# cellSwitcher_li_ion_V6.net
KiCad netlist of a schematic drawn in EAGLE
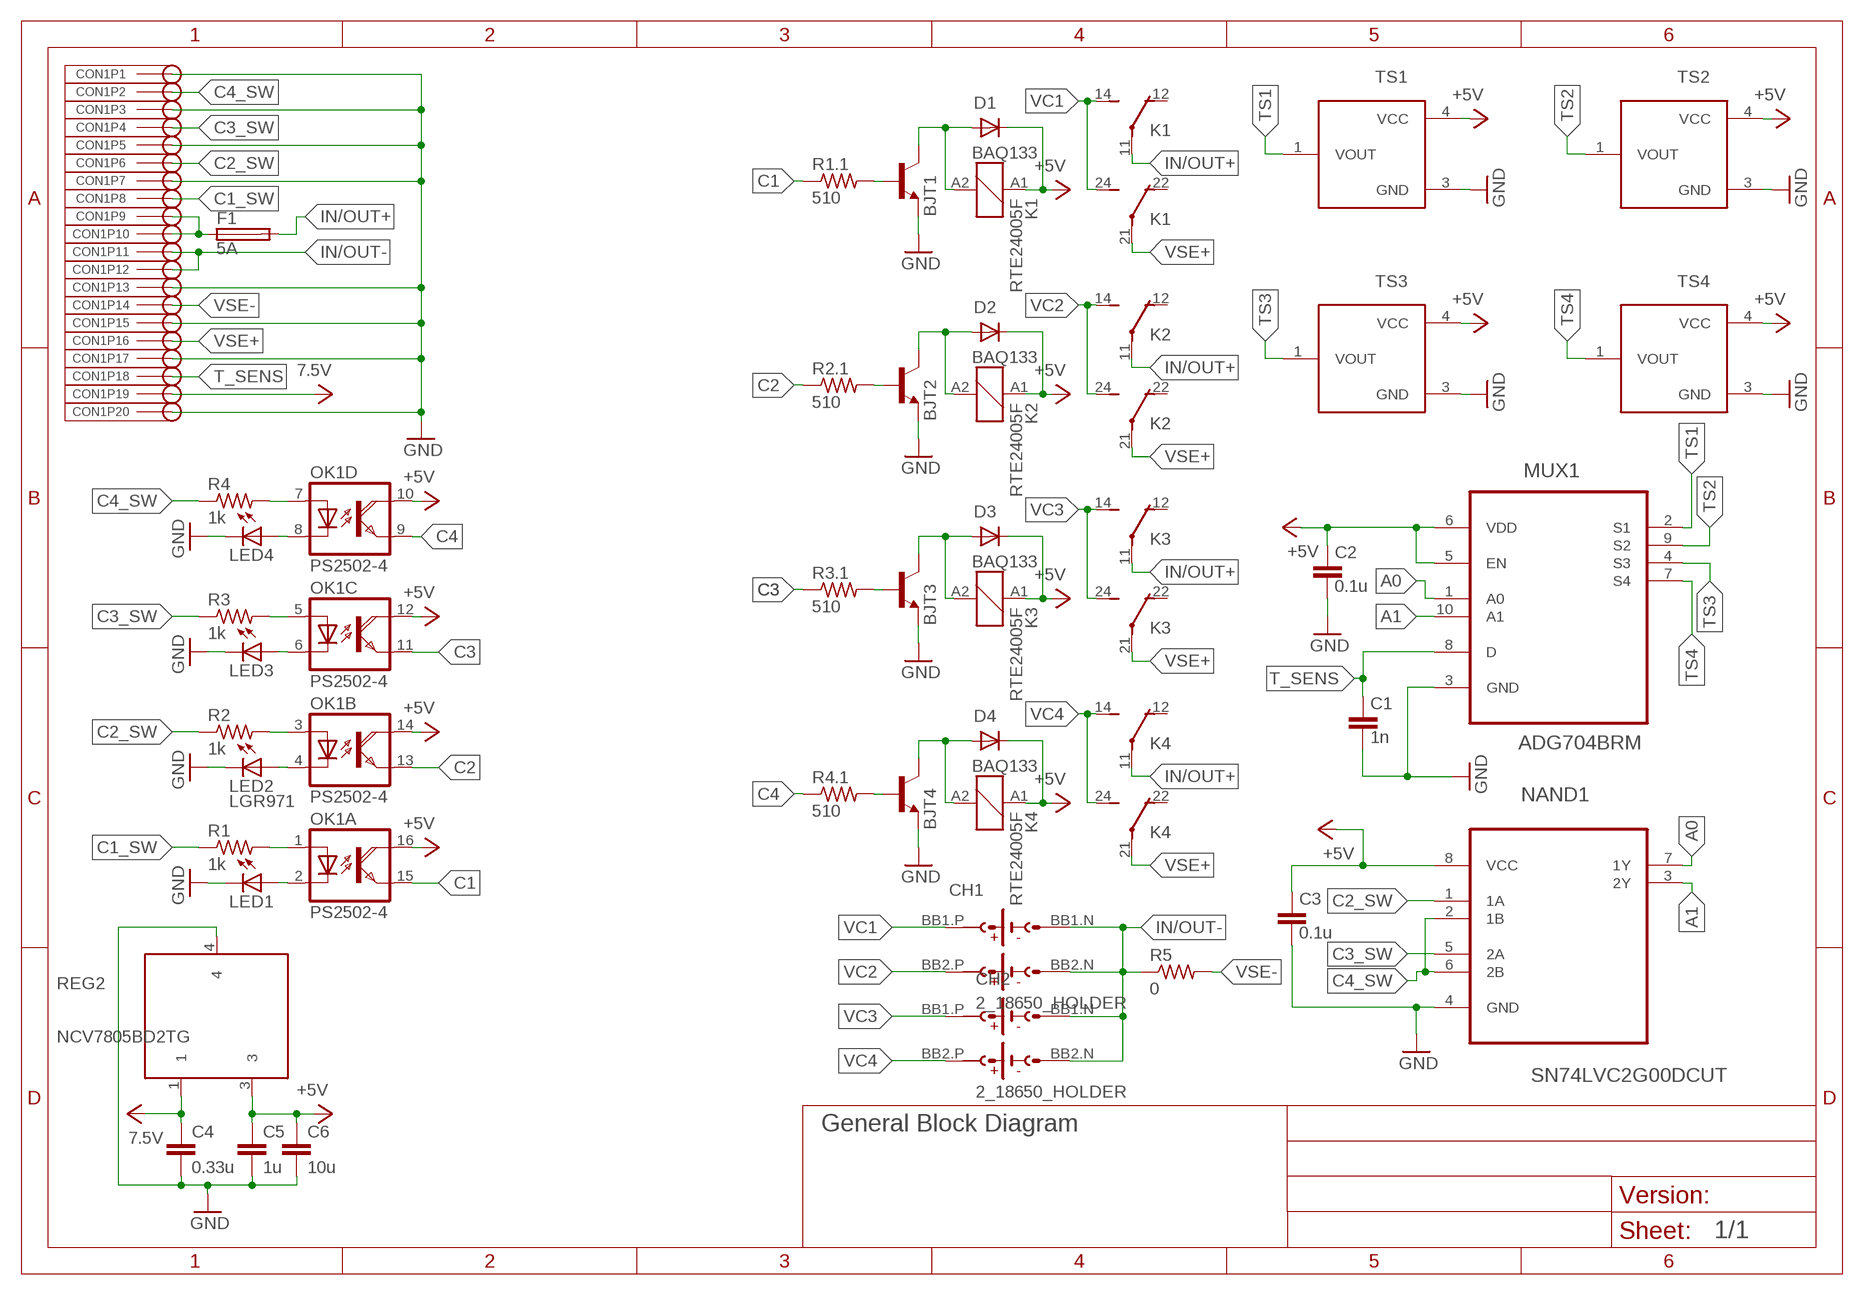
[diagram p0: schematic, sheet 1]

(export (version "E")
  (design (tool "Eeschema 10.0.6"))
  (components
    (comp (ref "BJT1")
      (value "BC818K-40")
      (footprint "eagle-import:SOT-23")
      (libsource (lib "eagle-import") (part "BC818K-40"))
    )
    (comp (ref "BJT2")
      (value "BC818K-40")
      (footprint "eagle-import:SOT-23")
      (libsource (lib "eagle-import") (part "BC818K-40"))
    )
    (comp (ref "BJT3")
      (value "BC818K-40")
      (footprint "eagle-import:SOT-23")
      (libsource (lib "eagle-import") (part "BC818K-40"))
    )
    (comp (ref "BJT4")
      (value "BC818K-40")
      (footprint "eagle-import:SOT-23")
      (libsource (lib "eagle-import") (part "BC818K-40"))
    )
    (comp (ref "C1")
      (value "1n")
      (footprint "eagle-import:C0603")
      (libsource (lib "eagle-import") (part "NONPOL_CAP-0603"))
    )
    (comp (ref "C2")
      (value "0.1u")
      (footprint "eagle-import:C0603")
      (libsource (lib "eagle-import") (part "NONPOL_CAP-0603"))
    )
    (comp (ref "C3")
      (value "0.1u")
      (footprint "eagle-import:C0603")
      (libsource (lib "eagle-import") (part "NONPOL_CAP-0603"))
    )
    (comp (ref "C4")
      (value "0.33u")
      (footprint "eagle-import:C0603")
      (libsource (lib "eagle-import") (part "NONPOL_CAP-0603"))
    )
    (comp (ref "C5")
      (value "1u")
      (footprint "eagle-import:C0603")
      (libsource (lib "eagle-import") (part "NONPOL_CAP-0603"))
    )
    (comp (ref "C6")
      (value "10u")
      (footprint "eagle-import:C0603")
      (libsource (lib "eagle-import") (part "NONPOL_CAP-0603"))
    )
    (comp (ref "CH1")
      (value "2_18650_HOLDER")
      (footprint "eagle-import:2_18650_HOLDER")
      (libsource (lib "eagle-import") (part "2_18650_HOLDER"))
    )
    (comp (ref "CH2")
      (value "2_18650_HOLDER")
      (footprint "eagle-import:2_18650_HOLDER")
      (libsource (lib "eagle-import") (part "2_18650_HOLDER"))
    )
    (comp (ref "CON1")
      (value "TMM-110-01-F-D-RA")
      (footprint "eagle-import:TMM-110-01-F-D-RA")
      (libsource (lib "eagle-import") (part "TMM-110-01-F-D-RA"))
    )
    (comp (ref "D1")
      (value "BAQ133")
      (footprint "eagle-import:SOD08")
      (libsource (lib "eagle-import") (part "DIODE-BAQ133-GS08"))
    )
    (comp (ref "D2")
      (value "BAQ133")
      (footprint "eagle-import:SOD08")
      (libsource (lib "eagle-import") (part "DIODE-BAQ133-GS08"))
    )
    (comp (ref "D3")
      (value "BAQ133")
      (footprint "eagle-import:SOD08")
      (libsource (lib "eagle-import") (part "DIODE-BAQ133-GS08"))
    )
    (comp (ref "D4")
      (value "BAQ133")
      (footprint "eagle-import:SOD08")
      (libsource (lib "eagle-import") (part "DIODE-BAQ133-GS08"))
    )
    (comp (ref "F1")
      (value "5A")
      (footprint "eagle-import:SH22,5")
      (fields (field (name "MF") "SCHURTER") (field (name "MPN") "0031.8201"))
      (libsource (lib "eagle-import") (part "FUSEHOLDER"))
    )
    (comp (ref "K1")
      (value "RTE24005F")
      (footprint "eagle-import:RTE24005F")
      (libsource (lib "eagle-import") (part "RTE24005F"))
    )
    (comp (ref "K2")
      (value "RTE24005F")
      (footprint "eagle-import:RTE24005F")
      (libsource (lib "eagle-import") (part "RTE24005F"))
    )
    (comp (ref "K3")
      (value "RTE24005F")
      (footprint "eagle-import:RTE24005F")
      (libsource (lib "eagle-import") (part "RTE24005F"))
    )
    (comp (ref "K4")
      (value "RTE24005F")
      (footprint "eagle-import:RTE24005F")
      (libsource (lib "eagle-import") (part "RTE24005F"))
    )
    (comp (ref "LED1")
      (value "LGR971")
      (footprint "eagle-import:SML0805")
      (libsource (lib "eagle-import") (part "LGR971"))
    )
    (comp (ref "LED2")
      (value "LGR971")
      (footprint "eagle-import:SML0805")
      (libsource (lib "eagle-import") (part "LGR971"))
    )
    (comp (ref "LED3")
      (value "LGR971")
      (footprint "eagle-import:SML0805")
      (libsource (lib "eagle-import") (part "LGR971"))
    )
    (comp (ref "LED4")
      (value "LGR971")
      (footprint "eagle-import:SML0805")
      (libsource (lib "eagle-import") (part "LGR971"))
    )
    (comp (ref "MUX1")
      (value "ADG704BRM")
      (footprint "eagle-import:MSOP10")
      (fields (field (name "MPN") "ADG704BRM-REEL"))
      (libsource (lib "eagle-import") (part "ADG704BRM"))
    )
    (comp (ref "NAND1")
      (value "SN74LVC2G00DCUT")
      (footprint "eagle-import:VSSOP-8")
      (libsource (lib "eagle-import") (part "SN74LVC2G00DCUT"))
    )
    (comp (ref "OK1")
      (value "PS2502-4")
      (footprint "eagle-import:DIL16")
      (libsource (lib "eagle-import") (part "PS2502-4"))
    )
    (comp (ref "R1")
      (value "1k")
      (footprint "eagle-import:R0603")
      (libsource (lib "eagle-import") (part "RESISTOR-0603"))
    )
    (comp (ref "R1.1")
      (value "510")
      (footprint "eagle-import:R0603")
      (libsource (lib "eagle-import") (part "RESISTOR-0603"))
    )
    (comp (ref "R2")
      (value "1k")
      (footprint "eagle-import:R0603")
      (libsource (lib "eagle-import") (part "RESISTOR-0603"))
    )
    (comp (ref "R2.1")
      (value "510")
      (footprint "eagle-import:R0603")
      (libsource (lib "eagle-import") (part "RESISTOR-0603"))
    )
    (comp (ref "R3")
      (value "1k")
      (footprint "eagle-import:R0603")
      (libsource (lib "eagle-import") (part "RESISTOR-0603"))
    )
    (comp (ref "R3.1")
      (value "510")
      (footprint "eagle-import:R0603")
      (libsource (lib "eagle-import") (part "RESISTOR-0603"))
    )
    (comp (ref "R4")
      (value "1k")
      (footprint "eagle-import:R0603")
      (libsource (lib "eagle-import") (part "RESISTOR-0603"))
    )
    (comp (ref "R4.1")
      (value "510")
      (footprint "eagle-import:R0603")
      (libsource (lib "eagle-import") (part "RESISTOR-0603"))
    )
    (comp (ref "R5")
      (value "0")
      (footprint "eagle-import:R0603")
      (libsource (lib "eagle-import") (part "RESISTOR-0603"))
    )
    (comp (ref "REG2")
      (value "NCV7805BD2TG")
      (footprint "eagle-import:D2PAK-3")
      (libsource (lib "eagle-import") (part "NCV7805BD2TG"))
    )
    (comp (ref "TS1")
      (value "STLM20DD9F")
      (footprint "eagle-import:UDFN-4L")
      (libsource (lib "eagle-import") (part "STLM20DD9F"))
    )
    (comp (ref "TS2")
      (value "STLM20DD9F")
      (footprint "eagle-import:UDFN-4L")
      (libsource (lib "eagle-import") (part "STLM20DD9F"))
    )
    (comp (ref "TS3")
      (value "STLM20DD9F")
      (footprint "eagle-import:UDFN-4L")
      (libsource (lib "eagle-import") (part "STLM20DD9F"))
    )
    (comp (ref "TS4")
      (value "STLM20DD9F")
      (footprint "eagle-import:UDFN-4L")
      (libsource (lib "eagle-import") (part "STLM20DD9F"))
    )
  )
  (nets
    (net (code "1") (name "+5V") (class "Default")
      (node (ref "C2") (pin "1") (pinfunction "1_1") (pintype "passive"))
      (node (ref "C3") (pin "1") (pinfunction "1_1") (pintype "passive"))
      (node (ref "C5") (pin "1") (pinfunction "1_1") (pintype "passive"))
      (node (ref "C6") (pin "1") (pinfunction "1_1") (pintype "passive"))
      (node (ref "D1") (pin "C") (pinfunction "C_C") (pintype "passive"))
      (node (ref "D2") (pin "C") (pinfunction "C_C") (pintype "passive"))
      (node (ref "D3") (pin "C") (pinfunction "C_C") (pintype "passive"))
      (node (ref "D4") (pin "C") (pinfunction "C_C") (pintype "passive"))
      (node (ref "K1") (pin "A1") (pinfunction "1_A1") (pintype "passive"))
      (node (ref "K2") (pin "A1") (pinfunction "1_A1") (pintype "passive"))
      (node (ref "K3") (pin "A1") (pinfunction "1_A1") (pintype "passive"))
      (node (ref "K4") (pin "A1") (pinfunction "1_A1") (pintype "passive"))
      (node (ref "MUX1") (pin "5") (pinfunction "EN_5") (pintype "input"))
      (node (ref "MUX1") (pin "6") (pinfunction "VDD_6") (pintype "power_in"))
      (node (ref "NAND1") (pin "8") (pinfunction "VCC_8") (pintype "power_in"))
      (node (ref "OK1") (pin "10") (pinfunction "COL_10") (pintype "passive"))
      (node (ref "OK1") (pin "12") (pinfunction "COL_12") (pintype "passive"))
      (node (ref "OK1") (pin "14") (pinfunction "COL_14") (pintype "passive"))
      (node (ref "OK1") (pin "16") (pinfunction "COL_16") (pintype "passive"))
      (node (ref "REG2") (pin "3") (pinfunction "3_3") (pintype "bidirectional"))
      (node (ref "TS1") (pin "4") (pinfunction "VCC_4") (pintype "bidirectional"))
      (node (ref "TS2") (pin "4") (pinfunction "VCC_4") (pintype "bidirectional"))
      (node (ref "TS3") (pin "4") (pinfunction "VCC_4") (pintype "bidirectional"))
      (node (ref "TS4") (pin "4") (pinfunction "VCC_4") (pintype "bidirectional"))
    )
    (net (code "2") (name "7.5V") (class "Default")
      (node (ref "C4") (pin "1") (pinfunction "1_1") (pintype "passive"))
      (node (ref "CON1") (pin "19") (pinfunction "PIN_19") (pintype "bidirectional"))
      (node (ref "REG2") (pin "1") (pinfunction "1_1") (pintype "bidirectional"))
    )
    (net (code "3") (name "A0") (class "Default")
      (node (ref "MUX1") (pin "1") (pinfunction "A0_1") (pintype "input"))
      (node (ref "NAND1") (pin "7") (pinfunction "1Y_7") (pintype "output"))
    )
    (net (code "4") (name "A1") (class "Default")
      (node (ref "MUX1") (pin "10") (pinfunction "A1_10") (pintype "input"))
      (node (ref "NAND1") (pin "3") (pinfunction "2Y_3") (pintype "output"))
    )
    (net (code "5") (name "C1") (class "Default")
      (node (ref "OK1") (pin "15") (pinfunction "EMI_15") (pintype "passive"))
      (node (ref "R1.1") (pin "1") (pinfunction "1_1") (pintype "passive"))
    )
    (net (code "6") (name "C1_SW") (class "Default")
      (node (ref "CON1") (pin "8") (pinfunction "PIN_8") (pintype "bidirectional"))
      (node (ref "R1") (pin "1") (pinfunction "1_1") (pintype "passive"))
    )
    (net (code "7") (name "C2") (class "Default")
      (node (ref "OK1") (pin "13") (pinfunction "EMI_13") (pintype "passive"))
      (node (ref "R2.1") (pin "1") (pinfunction "1_1") (pintype "passive"))
    )
    (net (code "8") (name "C2_SW") (class "Default")
      (node (ref "CON1") (pin "6") (pinfunction "PIN_6") (pintype "bidirectional"))
      (node (ref "NAND1") (pin "1") (pinfunction "1A_1") (pintype "input"))
      (node (ref "R2") (pin "1") (pinfunction "1_1") (pintype "passive"))
    )
    (net (code "9") (name "C3") (class "Default")
      (node (ref "OK1") (pin "11") (pinfunction "EMI_11") (pintype "passive"))
      (node (ref "R3.1") (pin "1") (pinfunction "1_1") (pintype "passive"))
    )
    (net (code "10") (name "C3_SW") (class "Default")
      (node (ref "CON1") (pin "4") (pinfunction "PIN_4") (pintype "bidirectional"))
      (node (ref "NAND1") (pin "5") (pinfunction "2A_5") (pintype "input"))
      (node (ref "R3") (pin "1") (pinfunction "1_1") (pintype "passive"))
    )
    (net (code "11") (name "C4") (class "Default")
      (node (ref "OK1") (pin "9") (pinfunction "EMI_9") (pintype "passive"))
      (node (ref "R4.1") (pin "1") (pinfunction "1_1") (pintype "passive"))
    )
    (net (code "12") (name "C4_SW") (class "Default")
      (node (ref "CON1") (pin "2") (pinfunction "PIN_2") (pintype "bidirectional"))
      (node (ref "NAND1") (pin "2") (pinfunction "1B_2") (pintype "input"))
      (node (ref "NAND1") (pin "6") (pinfunction "2B_6") (pintype "input"))
      (node (ref "R4") (pin "1") (pinfunction "1_1") (pintype "passive"))
    )
    (net (code "13") (name "GND") (class "Default")
      (node (ref "BJT1") (pin "2") (pinfunction "E_2") (pintype "passive"))
      (node (ref "BJT2") (pin "2") (pinfunction "E_2") (pintype "passive"))
      (node (ref "BJT3") (pin "2") (pinfunction "E_2") (pintype "passive"))
      (node (ref "BJT4") (pin "2") (pinfunction "E_2") (pintype "passive"))
      (node (ref "C1") (pin "2") (pinfunction "2_2") (pintype "passive"))
      (node (ref "C2") (pin "2") (pinfunction "2_2") (pintype "passive"))
      (node (ref "C3") (pin "2") (pinfunction "2_2") (pintype "passive"))
      (node (ref "C4") (pin "2") (pinfunction "2_2") (pintype "passive"))
      (node (ref "C5") (pin "2") (pinfunction "2_2") (pintype "passive"))
      (node (ref "C6") (pin "2") (pinfunction "2_2") (pintype "passive"))
      (node (ref "CON1") (pin "1") (pinfunction "PIN_1") (pintype "bidirectional"))
      (node (ref "CON1") (pin "13") (pinfunction "PIN_13") (pintype "bidirectional"))
      (node (ref "CON1") (pin "15") (pinfunction "PIN_15") (pintype "bidirectional"))
      (node (ref "CON1") (pin "17") (pinfunction "PIN_17") (pintype "bidirectional"))
      (node (ref "CON1") (pin "20") (pinfunction "PIN_20") (pintype "bidirectional"))
      (node (ref "CON1") (pin "3") (pinfunction "PIN_3") (pintype "bidirectional"))
      (node (ref "CON1") (pin "5") (pinfunction "PIN_5") (pintype "bidirectional"))
      (node (ref "CON1") (pin "7") (pinfunction "PIN_7") (pintype "bidirectional"))
      (node (ref "LED1") (pin "C") (pinfunction "C_C") (pintype "passive"))
      (node (ref "LED2") (pin "C") (pinfunction "C_C") (pintype "passive"))
      (node (ref "LED3") (pin "C") (pinfunction "C_C") (pintype "passive"))
      (node (ref "LED4") (pin "C") (pinfunction "C_C") (pintype "passive"))
      (node (ref "MUX1") (pin "3") (pinfunction "GND_3") (pintype "passive"))
      (node (ref "NAND1") (pin "4") (pinfunction "GND_4") (pintype "passive"))
      (node (ref "REG2") (pin "4") (pinfunction "4_4") (pintype "bidirectional"))
      (node (ref "TS1") (pin "3") (pinfunction "GND_3") (pintype "bidirectional"))
      (node (ref "TS2") (pin "3") (pinfunction "GND_3") (pintype "bidirectional"))
      (node (ref "TS3") (pin "3") (pinfunction "GND_3") (pintype "bidirectional"))
      (node (ref "TS4") (pin "3") (pinfunction "GND_3") (pintype "bidirectional"))
    )
    (net (code "14") (name "IN{slash}OUT+") (class "Default")
      (node (ref "F1") (pin "2") (pinfunction "2_2") (pintype "passive"))
      (node (ref "K1") (pin "11") (pinfunction "COM_11") (pintype "passive"))
      (node (ref "K2") (pin "11") (pinfunction "COM_11") (pintype "passive"))
      (node (ref "K3") (pin "11") (pinfunction "COM_11") (pintype "passive"))
      (node (ref "K4") (pin "11") (pinfunction "COM_11") (pintype "passive"))
    )
    (net (code "15") (name "IN{slash}OUT-") (class "Default")
      (node (ref "CH1") (pin "BB1.N") (pinfunction "B1.N_BB1.N") (pintype "bidirectional"))
      (node (ref "CH1") (pin "BB2.N") (pinfunction "B2.N_BB2.N") (pintype "bidirectional"))
      (node (ref "CH2") (pin "BB1.N") (pinfunction "B1.N_BB1.N") (pintype "bidirectional"))
      (node (ref "CH2") (pin "BB2.N") (pinfunction "B2.N_BB2.N") (pintype "bidirectional"))
      (node (ref "CON1") (pin "11") (pinfunction "PIN_11") (pintype "bidirectional"))
      (node (ref "CON1") (pin "12") (pinfunction "PIN_12") (pintype "bidirectional"))
      (node (ref "R5") (pin "1") (pinfunction "1_1") (pintype "passive"))
    )
    (net (code "16") (name "Net-(BJT1-B)") (class "Default")
      (node (ref "BJT1") (pin "1") (pinfunction "B_1") (pintype "passive"))
      (node (ref "R1.1") (pin "2") (pinfunction "2_2") (pintype "passive"))
    )
    (net (code "17") (name "Net-(BJT1-C)") (class "Default")
      (node (ref "BJT1") (pin "3") (pinfunction "C_3") (pintype "passive"))
      (node (ref "D1") (pin "A") (pinfunction "A_A") (pintype "passive"))
      (node (ref "K1") (pin "A2") (pinfunction "2_A2") (pintype "passive"))
    )
    (net (code "18") (name "Net-(BJT2-B)") (class "Default")
      (node (ref "BJT2") (pin "1") (pinfunction "B_1") (pintype "passive"))
      (node (ref "R2.1") (pin "2") (pinfunction "2_2") (pintype "passive"))
    )
    (net (code "19") (name "Net-(BJT2-C)") (class "Default")
      (node (ref "BJT2") (pin "3") (pinfunction "C_3") (pintype "passive"))
      (node (ref "D2") (pin "A") (pinfunction "A_A") (pintype "passive"))
      (node (ref "K2") (pin "A2") (pinfunction "2_A2") (pintype "passive"))
    )
    (net (code "20") (name "Net-(BJT3-B)") (class "Default")
      (node (ref "BJT3") (pin "1") (pinfunction "B_1") (pintype "passive"))
      (node (ref "R3.1") (pin "2") (pinfunction "2_2") (pintype "passive"))
    )
    (net (code "21") (name "Net-(BJT3-C)") (class "Default")
      (node (ref "BJT3") (pin "3") (pinfunction "C_3") (pintype "passive"))
      (node (ref "D3") (pin "A") (pinfunction "A_A") (pintype "passive"))
      (node (ref "K3") (pin "A2") (pinfunction "2_A2") (pintype "passive"))
    )
    (net (code "22") (name "Net-(BJT4-B)") (class "Default")
      (node (ref "BJT4") (pin "1") (pinfunction "B_1") (pintype "passive"))
      (node (ref "R4.1") (pin "2") (pinfunction "2_2") (pintype "passive"))
    )
    (net (code "23") (name "Net-(BJT4-C)") (class "Default")
      (node (ref "BJT4") (pin "3") (pinfunction "C_3") (pintype "passive"))
      (node (ref "D4") (pin "A") (pinfunction "A_A") (pintype "passive"))
      (node (ref "K4") (pin "A2") (pinfunction "2_A2") (pintype "passive"))
    )
    (net (code "24") (name "Net-(CON1B-PIN)") (class "Default")
      (node (ref "CON1") (pin "10") (pinfunction "PIN_10") (pintype "bidirectional"))
      (node (ref "CON1") (pin "9") (pinfunction "PIN_9") (pintype "bidirectional"))
      (node (ref "F1") (pin "1") (pinfunction "1_1") (pintype "passive"))
    )
    (net (code "25") (name "Net-(OK1A-A)") (class "Default")
      (node (ref "OK1") (pin "1") (pinfunction "A_1") (pintype "passive"))
      (node (ref "R1") (pin "2") (pinfunction "2_2") (pintype "passive"))
    )
    (net (code "26") (name "Net-(OK1A-C)") (class "Default")
      (node (ref "LED1") (pin "A") (pinfunction "A_A") (pintype "passive"))
      (node (ref "OK1") (pin "2") (pinfunction "C_2") (pintype "passive"))
    )
    (net (code "27") (name "Net-(OK1B-A)") (class "Default")
      (node (ref "OK1") (pin "3") (pinfunction "A_3") (pintype "passive"))
      (node (ref "R2") (pin "2") (pinfunction "2_2") (pintype "passive"))
    )
    (net (code "28") (name "Net-(OK1B-C)") (class "Default")
      (node (ref "LED2") (pin "A") (pinfunction "A_A") (pintype "passive"))
      (node (ref "OK1") (pin "4") (pinfunction "C_4") (pintype "passive"))
    )
    (net (code "29") (name "Net-(OK1C-A)") (class "Default")
      (node (ref "OK1") (pin "5") (pinfunction "A_5") (pintype "passive"))
      (node (ref "R3") (pin "2") (pinfunction "2_2") (pintype "passive"))
    )
    (net (code "30") (name "Net-(OK1C-C)") (class "Default")
      (node (ref "LED3") (pin "A") (pinfunction "A_A") (pintype "passive"))
      (node (ref "OK1") (pin "6") (pinfunction "C_6") (pintype "passive"))
    )
    (net (code "31") (name "Net-(OK1D-A)") (class "Default")
      (node (ref "OK1") (pin "7") (pinfunction "A_7") (pintype "passive"))
      (node (ref "R4") (pin "2") (pinfunction "2_2") (pintype "passive"))
    )
    (net (code "32") (name "Net-(OK1D-C)") (class "Default")
      (node (ref "LED4") (pin "A") (pinfunction "A_A") (pintype "passive"))
      (node (ref "OK1") (pin "8") (pinfunction "C_8") (pintype "passive"))
    )
    (net (code "33") (name "TS1") (class "Default")
      (node (ref "MUX1") (pin "2") (pinfunction "S1_2") (pintype "bidirectional"))
      (node (ref "TS1") (pin "1") (pinfunction "VOUT_1") (pintype "bidirectional"))
    )
    (net (code "34") (name "TS2") (class "Default")
      (node (ref "MUX1") (pin "9") (pinfunction "S2_9") (pintype "bidirectional"))
      (node (ref "TS2") (pin "1") (pinfunction "VOUT_1") (pintype "bidirectional"))
    )
    (net (code "35") (name "TS3") (class "Default")
      (node (ref "MUX1") (pin "4") (pinfunction "S3_4") (pintype "bidirectional"))
      (node (ref "TS3") (pin "1") (pinfunction "VOUT_1") (pintype "bidirectional"))
    )
    (net (code "36") (name "TS4") (class "Default")
      (node (ref "MUX1") (pin "7") (pinfunction "S4_7") (pintype "bidirectional"))
      (node (ref "TS4") (pin "1") (pinfunction "VOUT_1") (pintype "bidirectional"))
    )
    (net (code "37") (name "T_SENS") (class "Default")
      (node (ref "C1") (pin "1") (pinfunction "1_1") (pintype "passive"))
      (node (ref "CON1") (pin "18") (pinfunction "PIN_18") (pintype "bidirectional"))
      (node (ref "MUX1") (pin "8") (pinfunction "D_8") (pintype "bidirectional"))
    )
    (net (code "38") (name "VC1") (class "Default")
      (node (ref "CH1") (pin "BB1.P") (pinfunction "B1.P_BB1.P") (pintype "bidirectional"))
      (node (ref "K1") (pin "14") (pinfunction "NO_14") (pintype "passive"))
      (node (ref "K1") (pin "24") (pinfunction "NO_24") (pintype "passive"))
    )
    (net (code "39") (name "VC2") (class "Default")
      (node (ref "CH1") (pin "BB2.P") (pinfunction "B2.P_BB2.P") (pintype "bidirectional"))
      (node (ref "K2") (pin "14") (pinfunction "NO_14") (pintype "passive"))
      (node (ref "K2") (pin "24") (pinfunction "NO_24") (pintype "passive"))
    )
    (net (code "40") (name "VC3") (class "Default")
      (node (ref "CH2") (pin "BB1.P") (pinfunction "B1.P_BB1.P") (pintype "bidirectional"))
      (node (ref "K3") (pin "14") (pinfunction "NO_14") (pintype "passive"))
      (node (ref "K3") (pin "24") (pinfunction "NO_24") (pintype "passive"))
    )
    (net (code "41") (name "VC4") (class "Default")
      (node (ref "CH2") (pin "BB2.P") (pinfunction "B2.P_BB2.P") (pintype "bidirectional"))
      (node (ref "K4") (pin "14") (pinfunction "NO_14") (pintype "passive"))
      (node (ref "K4") (pin "24") (pinfunction "NO_24") (pintype "passive"))
    )
    (net (code "42") (name "VSE+") (class "Default")
      (node (ref "CON1") (pin "16") (pinfunction "PIN_16") (pintype "bidirectional"))
      (node (ref "K1") (pin "21") (pinfunction "COM_21") (pintype "passive"))
      (node (ref "K2") (pin "21") (pinfunction "COM_21") (pintype "passive"))
      (node (ref "K3") (pin "21") (pinfunction "COM_21") (pintype "passive"))
      (node (ref "K4") (pin "21") (pinfunction "COM_21") (pintype "passive"))
    )
    (net (code "43") (name "VSE-") (class "Default")
      (node (ref "CON1") (pin "14") (pinfunction "PIN_14") (pintype "bidirectional"))
      (node (ref "R5") (pin "2") (pinfunction "2_2") (pintype "passive"))
    )
    (net (code "44") (name "unconnected-(K1B-NC-Pad12)") (class "Default")
      (node (ref "K1") (pin "12") (pinfunction "NC_12") (pintype "passive"))
    )
    (net (code "45") (name "unconnected-(K1C-NC-Pad22)") (class "Default")
      (node (ref "K1") (pin "22") (pinfunction "NC_22") (pintype "passive"))
    )
    (net (code "46") (name "unconnected-(K2B-NC-Pad12)") (class "Default")
      (node (ref "K2") (pin "12") (pinfunction "NC_12") (pintype "passive"))
    )
    (net (code "47") (name "unconnected-(K2C-NC-Pad22)") (class "Default")
      (node (ref "K2") (pin "22") (pinfunction "NC_22") (pintype "passive"))
    )
    (net (code "48") (name "unconnected-(K3B-NC-Pad12)") (class "Default")
      (node (ref "K3") (pin "12") (pinfunction "NC_12") (pintype "passive"))
    )
    (net (code "49") (name "unconnected-(K3C-NC-Pad22)") (class "Default")
      (node (ref "K3") (pin "22") (pinfunction "NC_22") (pintype "passive"))
    )
    (net (code "50") (name "unconnected-(K4B-NC-Pad12)") (class "Default")
      (node (ref "K4") (pin "12") (pinfunction "NC_12") (pintype "passive"))
    )
    (net (code "51") (name "unconnected-(K4C-NC-Pad22)") (class "Default")
      (node (ref "K4") (pin "22") (pinfunction "NC_22") (pintype "passive"))
    )
  )
)
